# protection.net
KiCad netlist of a schematic drawn in Altium Designer
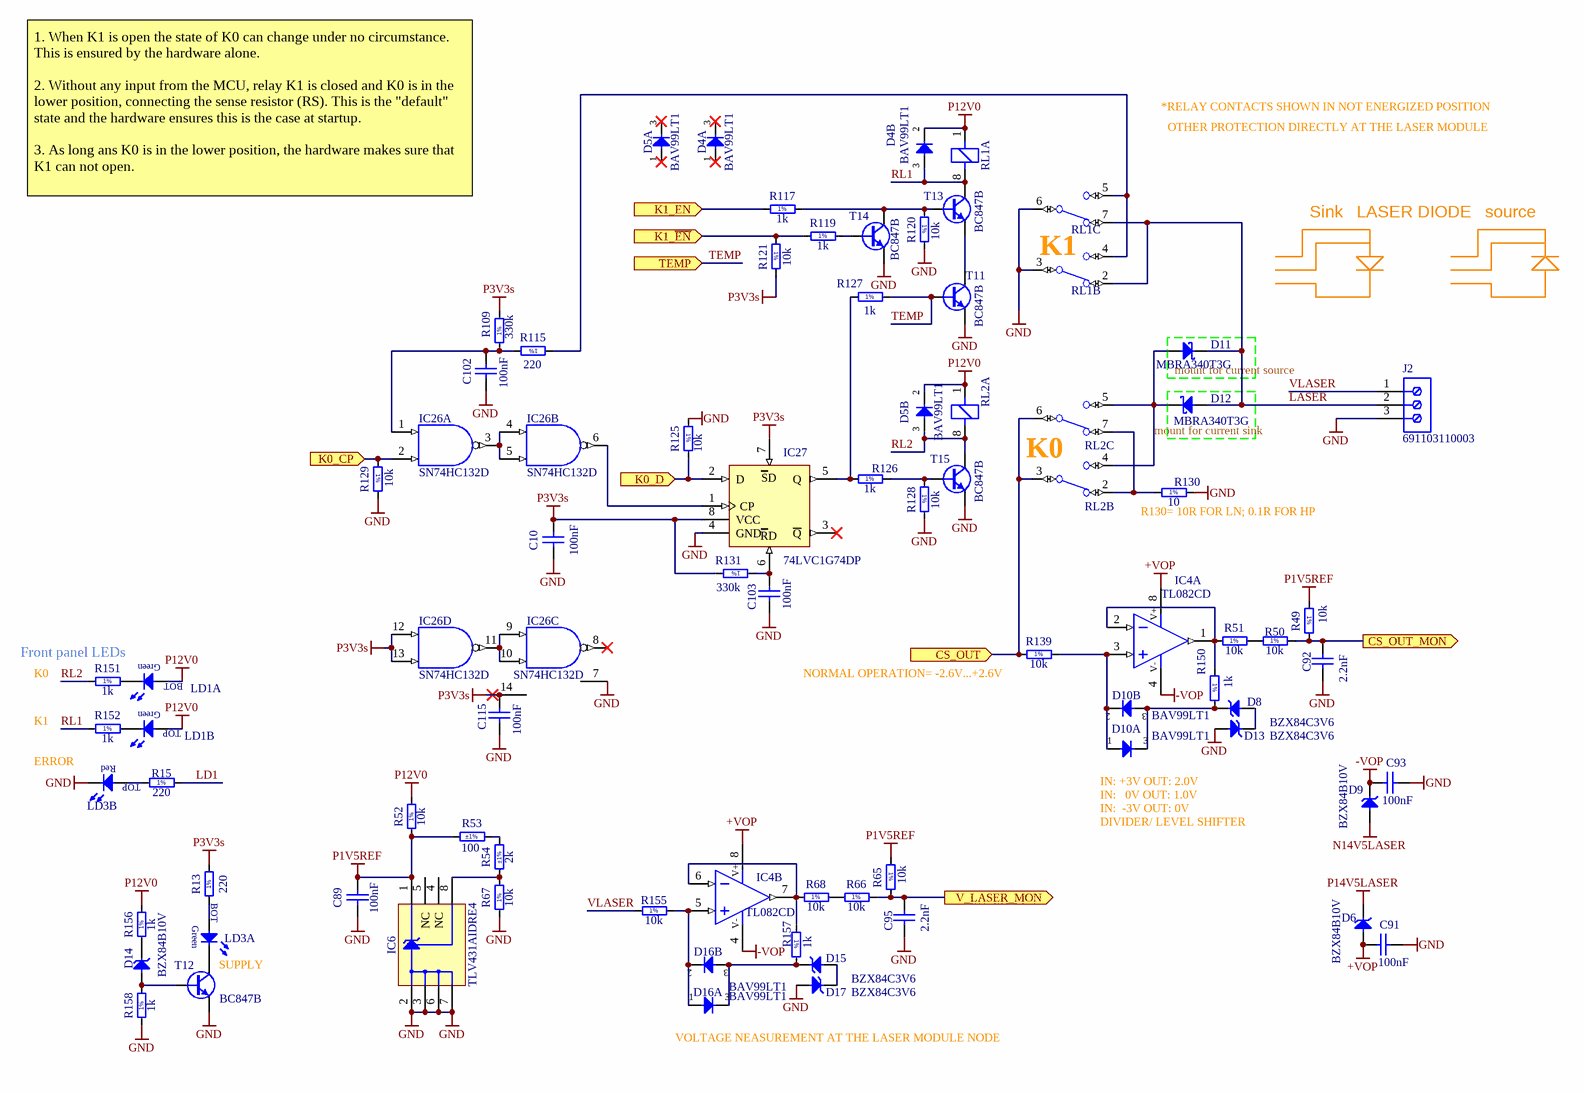
[diagram p0: protection.SchDoc]

(export (version "E")
  (design (tool "Eeschema 10.0.6"))
  (components
    (comp (ref "C10")
      (value "100nF")
      (footprint "CAPC1608X87N")
      (description "Non-polarised capacitor")
      (fields
        (field (name "PART NUMBER") "CC0603_100NF_50V_10%_X7R")
        (field (name "VOLTAGE") "50V")
        (field (name "AUTHOR") "CERN DEM JLC")
      )
      (libsource (lib "Capacitors") (part "Capacitor - non polarized"))
    )
    (comp (ref "C89")
      (value "100nF")
      (footprint "CAPC1608X87N")
      (description "Non-polarised capacitor")
      (fields
        (field (name "PART NUMBER") "CC0603_100NF_50V_10%_X7R")
        (field (name "VOLTAGE") "50V")
        (field (name "AUTHOR") "CERN DEM JLC")
      )
      (libsource (lib "Capacitors") (part "Capacitor - non polarized"))
    )
    (comp (ref "C91")
      (value "100nF")
      (footprint "CAPC1608X87N")
      (description "Non-polarised capacitor")
      (fields
        (field (name "PART NUMBER") "CC0603_100NF_50V_10%_X7R")
        (field (name "VOLTAGE") "50V")
        (field (name "AUTHOR") "CERN DEM JLC")
      )
      (libsource (lib "Capacitors") (part "Capacitor - non polarized"))
    )
    (comp (ref "C92")
      (value "2.2nF")
      (footprint "CAPC1608X87N")
      (description "Non-polarised capacitor")
      (fields
        (field (name "PART NUMBER") "CC0603_2.2NF_50V_5%_C0G")
        (field (name "VOLTAGE") "50V")
        (field (name "AUTHOR") "CERN DEM JMW")
      )
      (libsource (lib "Capacitors") (part "Capacitor - non polarized"))
    )
    (comp (ref "C93")
      (value "100nF")
      (footprint "CAPC1608X87N")
      (description "Non-polarised capacitor")
      (fields
        (field (name "PART NUMBER") "CC0603_100NF_50V_10%_X7R")
        (field (name "VOLTAGE") "50V")
        (field (name "AUTHOR") "CERN DEM JLC")
      )
      (libsource (lib "Capacitors") (part "Capacitor - non polarized"))
    )
    (comp (ref "C95")
      (value "2.2nF")
      (footprint "CAPC1608X87N")
      (description "Non-polarised capacitor")
      (fields
        (field (name "PART NUMBER") "CC0603_2.2NF_50V_5%_C0G")
        (field (name "VOLTAGE") "50V")
        (field (name "AUTHOR") "CERN DEM JMW")
      )
      (libsource (lib "Capacitors") (part "Capacitor - non polarized"))
    )
    (comp (ref "C102")
      (value "100nF")
      (footprint "CAPC1608X87N")
      (description "Non-polarised capacitor")
      (fields
        (field (name "PART NUMBER") "CC0603_100NF_50V_10%_X7R")
        (field (name "VOLTAGE") "50V")
        (field (name "AUTHOR") "CERN DEM JLC")
      )
      (libsource (lib "Capacitors") (part "Capacitor - non polarized"))
    )
    (comp (ref "C103")
      (value "100nF")
      (footprint "CAPC1608X87N")
      (description "Non-polarised capacitor")
      (fields
        (field (name "PART NUMBER") "CC0603_100NF_50V_10%_X7R")
        (field (name "VOLTAGE") "50V")
        (field (name "AUTHOR") "CERN DEM JLC")
      )
      (libsource (lib "Capacitors") (part "Capacitor - non polarized"))
    )
    (comp (ref "C115")
      (value "100nF")
      (footprint "CAPC1608X87N")
      (description "Non-polarised capacitor")
      (fields
        (field (name "PART NUMBER") "CC0603_100NF_50V_10%_X7R")
        (field (name "VOLTAGE") "50V")
        (field (name "AUTHOR") "CERN DEM JLC")
      )
      (libsource (lib "Capacitors") (part "Capacitor - non polarized"))
    )
    (comp (ref "D4")
      (value "BAV99LT1")
      (footprint "SOT95P240X110-3N")
      (description "Serial Diode")
      (fields
        (field (name "VOLTAGE") "70V")
        (field (name "POWER") "225mW")
        (field (name "AUTHOR") "CERN DEM JLC")
      )
      (libsource (lib "ICs And Semiconductors") (part "Diode x2 A1C3_A3C2"))
    )
    (comp (ref "D5")
      (value "BAV99LT1")
      (footprint "SOT95P240X110-3N")
      (description "Serial Diode")
      (fields
        (field (name "VOLTAGE") "70V")
        (field (name "POWER") "225mW")
        (field (name "AUTHOR") "CERN DEM JLC")
      )
      (libsource (lib "ICs And Semiconductors") (part "Diode x2 A1C3_A3C2"))
    )
    (comp (ref "D6")
      (value "BZX84B10V")
      (footprint "SOT95P248X115-3N")
      (description "Diode Zener Anode Pin 1 Cathode Pin 3 (Pas de pin 2)")
      (fields
        (field (name "VOLTAGE") "10V")
        (field (name "POWER") "300mW")
        (field (name "AUTHOR") "CERN DEM JLC")
      )
      (libsource (lib "ICs And Semiconductors") (part "Diode Zener A1C3"))
    )
    (comp (ref "D8")
      (value "BZX84C3V6")
      (footprint "SOT95P240X130-3N")
      (description "Diode Zener Anode Pin 1 Cathode Pin 3 (Pas de pin 2)")
      (fields
        (field (name "VOLTAGE") "3V6")
        (field (name "POWER") "350mW")
        (field (name "AUTHOR") "CERN DEM JLC")
      )
      (libsource (lib "ICs And Semiconductors") (part "Diode Zener A1C3"))
    )
    (comp (ref "D9")
      (value "BZX84B10V")
      (footprint "SOT95P248X115-3N")
      (description "Diode Zener Anode Pin 1 Cathode Pin 3 (Pas de pin 2)")
      (fields
        (field (name "VOLTAGE") "10V")
        (field (name "POWER") "300mW")
        (field (name "AUTHOR") "CERN DEM JLC")
      )
      (libsource (lib "ICs And Semiconductors") (part "Diode Zener A1C3"))
    )
    (comp (ref "D10")
      (value "BAV99LT1")
      (footprint "SOT95P240X110-3N")
      (description "Serial Diode")
      (fields
        (field (name "VOLTAGE") "70V")
        (field (name "POWER") "225mW")
        (field (name "AUTHOR") "CERN DEM JLC")
      )
      (libsource (lib "ICs And Semiconductors") (part "Diode x2 A1C3_A3C2"))
    )
    (comp (ref "D11")
      (value "MBRA340T3G")
      (footprint "DIOM5226X220N")
      (description "Schottky Diode")
      (fields
        (field (name "VOLTAGE") "40V")
        (field (name "POWER") "3A")
        (field (name "AUTHOR") "CERN DEM JLC")
      )
      (libsource (lib "ICs And Semiconductors") (part "Diode Schottky"))
    )
    (comp (ref "D12")
      (value "MBRA340T3G")
      (footprint "DIOM5226X220N")
      (description "Schottky Diode")
      (fields
        (field (name "VOLTAGE") "40V")
        (field (name "POWER") "3A")
        (field (name "AUTHOR") "CERN DEM JLC")
      )
      (libsource (lib "ICs And Semiconductors") (part "Diode Schottky"))
    )
    (comp (ref "D13")
      (value "BZX84C3V6")
      (footprint "SOT95P240X130-3N")
      (description "Diode Zener Anode Pin 1 Cathode Pin 3 (Pas de pin 2)")
      (fields
        (field (name "VOLTAGE") "3V6")
        (field (name "POWER") "350mW")
        (field (name "AUTHOR") "CERN DEM JLC")
      )
      (libsource (lib "ICs And Semiconductors") (part "Diode Zener A1C3"))
    )
    (comp (ref "D14")
      (value "BZX84B10V")
      (footprint "SOT95P248X115-3N")
      (description "Diode Zener Anode Pin 1 Cathode Pin 3 (Pas de pin 2)")
      (fields
        (field (name "VOLTAGE") "10V")
        (field (name "POWER") "300mW")
        (field (name "AUTHOR") "CERN DEM JLC")
      )
      (libsource (lib "ICs And Semiconductors") (part "Diode Zener A1C3"))
    )
    (comp (ref "D15")
      (value "BZX84C3V6")
      (footprint "SOT95P240X130-3N")
      (description "Diode Zener Anode Pin 1 Cathode Pin 3 (Pas de pin 2)")
      (fields
        (field (name "VOLTAGE") "3V6")
        (field (name "POWER") "350mW")
        (field (name "AUTHOR") "CERN DEM JLC")
      )
      (libsource (lib "ICs And Semiconductors") (part "Diode Zener A1C3"))
    )
    (comp (ref "D16")
      (value "BAV99LT1")
      (footprint "SOT95P240X110-3N")
      (description "Serial Diode")
      (fields
        (field (name "VOLTAGE") "70V")
        (field (name "POWER") "225mW")
        (field (name "AUTHOR") "CERN DEM JLC")
      )
      (libsource (lib "ICs And Semiconductors") (part "Diode x2 A1C3_A3C2"))
    )
    (comp (ref "D17")
      (value "BZX84C3V6")
      (footprint "SOT95P240X130-3N")
      (description "Diode Zener Anode Pin 1 Cathode Pin 3 (Pas de pin 2)")
      (fields
        (field (name "VOLTAGE") "3V6")
        (field (name "POWER") "350mW")
        (field (name "AUTHOR") "CERN DEM JLC")
      )
      (libsource (lib "ICs And Semiconductors") (part "Diode Zener A1C3"))
    )
    (comp (ref "IC4")
      (value "TL082CD")
      (footprint "SOIC127P600X175-8N")
      (description "Dual Operational Amplifier")
      (fields (field (name "MANUFACTURER") "TEXAS INSTRUMENTS") (field (name "AUTHOR") "CERN DEM JLC"))
      (libsource (lib "ICs And Semiconductors") (part "Operational Amplifier x2 Type1"))
    )
    (comp (ref "IC6")
      (value "TLV431AIDRE4")
      (footprint "SOIC127P600X175-8N")
      (description "Precision Programmable Reference")
      (fields (field (name "MANUFACTURER") "TEXAS INSTRUMENTS") (field (name "AUTHOR") "CERN DEM JLC"))
      (libsource (lib "ICs And Semiconductors") (part "TL431xD"))
    )
    (comp (ref "IC26")
      (value "SN74HC132D")
      (footprint "SOIC127P600X175-14N")
      (description "Quad Positive NAND Gate With Schmitt-Trigger Input")
      (fields (field (name "MANUFACTURER") "TEXAS INSTRUMENTS") (field (name "AUTHOR") "CERN DEM JLC"))
      (libsource (lib "") (part "74132_1"))
    )
    (comp (ref "IC27")
      (value "74LVC1G74DP")
      (footprint "SOP65P400X110-8N")
      (description "Single D-type flip-flop with set and reset, positive edge trigger")
      (fields (field (name "MANUFACTURER") "NXP SEMICONDUCTORS") (field (name "AUTHOR") "CERN DEM JLC"))
      (libsource (lib "ICs And Semiconductors") (part "741G74"))
    )
    (comp (ref "J2")
      (value "691103110003")
      (footprint "691103110003")
      (description "WR-TBL Serie 1031 Horizontal Entry Modular, Pressure Clamp, THT, pitch 3.5mm, 3p")
      (fields (field (name "MANUFACTURER") "Wurth Elektronik"))
      (libsource (lib "Altium_WR-TBL (rev21a)") (part "691103110003"))
    )
    (comp (ref "LD1")
      (value "Green/Green")
      (footprint "LED_DIALIGHT_571-0122F")
      (description "LED x2 Green 1C2A-BOT_3C4A-TOP")
      (fields
        (field (name "PART NUMBER") "LED_DIALIGHT_571-0122F")
        (field (name "MANUFACTURER") "DIALIGHT")
        (field (name "AUTHOR") "CERN DEM JLC")
      )
      (libsource (lib "ICs And Semiconductors") (part "LED x2 Green 1C2A-BOT_3C4A-TOP"))
    )
    (comp (ref "LD3")
      (value "Red/Green")
      (footprint "LED_DIALIGHT_571-0112F")
      (description "2x LED  Botom Green, Top Red")
      (fields
        (field (name "PART NUMBER") "LED_DIALIGHT_571-0112F")
        (field (name "MANUFACTURER") "DIALIGHT")
        (field (name "AUTHOR") "CERN DEM JLC")
      )
      (libsource (lib "ICs And Semiconductors") (part "LED x2 G-1C2A-BOT_R-3C4A-TOP"))
    )
    (comp (ref "R13")
      (value "220")
      (footprint "RESC1608X55N")
      (description "Resistor - 1%")
      (fields
        (field (name "PART NUMBER") "R0603_220R_1%_0.1W_100PPM")
        (field (name "POWER") "0.1W")
        (field (name "AUTHOR") "CERN DEM JLC")
      )
      (libsource (lib "Resistors") (part "Resistor - 1%"))
    )
    (comp (ref "R15")
      (value "220")
      (footprint "RESC1608X55N")
      (description "Resistor - 1%")
      (fields
        (field (name "PART NUMBER") "R0603_220R_1%_0.1W_100PPM")
        (field (name "POWER") "0.1W")
        (field (name "AUTHOR") "CERN DEM JLC")
      )
      (libsource (lib "Resistors") (part "Resistor - 1%"))
    )
    (comp (ref "R49")
      (value "10k")
      (footprint "RESC1608X55N")
      (description "Resistor - 1%")
      (fields
        (field (name "PART NUMBER") "R0603_10K_1%_0.1W_100PPM")
        (field (name "POWER") "0.1W")
        (field (name "AUTHOR") "CERN DEM JLC")
      )
      (libsource (lib "Resistors") (part "Resistor - 1%"))
    )
    (comp (ref "R50")
      (value "10k")
      (footprint "RESC1608X55N")
      (description "Resistor - 1%")
      (fields
        (field (name "PART NUMBER") "R0603_10K_1%_0.1W_100PPM")
        (field (name "POWER") "0.1W")
        (field (name "AUTHOR") "CERN DEM JLC")
      )
      (libsource (lib "Resistors") (part "Resistor - 1%"))
    )
    (comp (ref "R51")
      (value "10k")
      (footprint "RESC1608X55N")
      (description "Resistor - 1%")
      (fields
        (field (name "PART NUMBER") "R0603_10K_1%_0.1W_100PPM")
        (field (name "POWER") "0.1W")
        (field (name "AUTHOR") "CERN DEM JLC")
      )
      (libsource (lib "Resistors") (part "Resistor - 1%"))
    )
    (comp (ref "R52")
      (value "10k")
      (footprint "RESC1608X55N")
      (description "Resistor - 1%")
      (fields
        (field (name "PART NUMBER") "R0603_10K_1%_0.1W_100PPM")
        (field (name "POWER") "0.1W")
        (field (name "AUTHOR") "CERN DEM JLC")
      )
      (libsource (lib "Resistors") (part "Resistor - 1%"))
    )
    (comp (ref "R53")
      (value "100")
      (footprint "RESC1608X55N")
      (description "Resistor - 1%")
      (fields
        (field (name "TOLERANCE") "±1%")
        (field (name "PART NUMBER") "R0603_100R_1%_0.1W_100PPM")
        (field (name "POWER") "0.1W")
        (field (name "AUTHOR") "CERN DEM JLC")
      )
      (libsource (lib "Resistors") (part "Resistor - 1%"))
    )
    (comp (ref "R54")
      (value "2k")
      (footprint "RESC1608X55N")
      (description "Resistor - 1%")
      (fields
        (field (name "TOLERANCE") "±1%")
        (field (name "PART NUMBER") "R0603_2K_1%_0.1W_100PPM")
        (field (name "POWER") "0.1W")
        (field (name "AUTHOR") "CERN DEM JLC")
      )
      (libsource (lib "Resistors") (part "Resistor - 1%"))
    )
    (comp (ref "R65")
      (value "10k")
      (footprint "RESC1608X55N")
      (description "Resistor - 1%")
      (fields
        (field (name "PART NUMBER") "R0603_10K_1%_0.1W_100PPM")
        (field (name "POWER") "0.1W")
        (field (name "AUTHOR") "CERN DEM JLC")
      )
      (libsource (lib "Resistors") (part "Resistor - 1%"))
    )
    (comp (ref "R66")
      (value "10k")
      (footprint "RESC1608X55N")
      (description "Resistor - 1%")
      (fields
        (field (name "PART NUMBER") "R0603_10K_1%_0.1W_100PPM")
        (field (name "POWER") "0.1W")
        (field (name "AUTHOR") "CERN DEM JLC")
      )
      (libsource (lib "Resistors") (part "Resistor - 1%"))
    )
    (comp (ref "R67")
      (value "10k")
      (footprint "RESC1608X55N")
      (description "Resistor - 1%")
      (fields
        (field (name "PART NUMBER") "R0603_10K_1%_0.1W_100PPM")
        (field (name "POWER") "0.1W")
        (field (name "AUTHOR") "CERN DEM JLC")
      )
      (libsource (lib "Resistors") (part "Resistor - 1%"))
    )
    (comp (ref "R68")
      (value "10k")
      (footprint "RESC1608X55N")
      (description "Resistor - 1%")
      (fields
        (field (name "PART NUMBER") "R0603_10K_1%_0.1W_100PPM")
        (field (name "POWER") "0.1W")
        (field (name "AUTHOR") "CERN DEM JLC")
      )
      (libsource (lib "Resistors") (part "Resistor - 1%"))
    )
    (comp (ref "R109")
      (value "330k")
      (footprint "RESC1608X55N")
      (description "Resistor - 1%")
      (fields
        (field (name "PART NUMBER") "R0603_330K_1%_0.1W_100PPM")
        (field (name "POWER") "0.1W")
        (field (name "AUTHOR") "CERN DEM JLC")
      )
      (libsource (lib "Resistors") (part "Resistor - 1%"))
    )
    (comp (ref "R115")
      (value "220")
      (footprint "RESC1608X55N")
      (description "Resistor - 1%")
      (fields
        (field (name "PART NUMBER") "R0603_220R_1%_0.1W_100PPM")
        (field (name "POWER") "0.1W")
        (field (name "AUTHOR") "CERN DEM JLC")
      )
      (libsource (lib "Resistors") (part "Resistor - 1%"))
    )
    (comp (ref "R117")
      (value "1k")
      (footprint "RESC1608X55N")
      (description "Resistor - 1%")
      (fields
        (field (name "PART NUMBER") "R0603_1K_1%_0.1W_100PPM")
        (field (name "POWER") "0.1W")
        (field (name "AUTHOR") "CERN DEM JLC")
      )
      (libsource (lib "Resistors") (part "Resistor - 1%"))
    )
    (comp (ref "R119")
      (value "1k")
      (footprint "RESC1608X55N")
      (description "Resistor - 1%")
      (fields
        (field (name "PART NUMBER") "R0603_1K_1%_0.1W_100PPM")
        (field (name "POWER") "0.1W")
        (field (name "AUTHOR") "CERN DEM JLC")
      )
      (libsource (lib "Resistors") (part "Resistor - 1%"))
    )
    (comp (ref "R120")
      (value "10k")
      (footprint "RESC1608X55N")
      (description "Resistor - 1%")
      (fields
        (field (name "PART NUMBER") "R0603_10K_1%_0.1W_100PPM")
        (field (name "POWER") "0.1W")
        (field (name "AUTHOR") "CERN DEM JLC")
      )
      (libsource (lib "Resistors") (part "Resistor - 1%"))
    )
    (comp (ref "R121")
      (value "10k")
      (footprint "RESC1608X55N")
      (description "Resistor - 1%")
      (fields
        (field (name "PART NUMBER") "R0603_10K_1%_0.1W_100PPM")
        (field (name "POWER") "0.1W")
        (field (name "AUTHOR") "CERN DEM JLC")
      )
      (libsource (lib "Resistors") (part "Resistor - 1%"))
    )
    (comp (ref "R125")
      (value "10k")
      (footprint "RESC1608X55N")
      (description "Resistor - 1%")
      (fields
        (field (name "PART NUMBER") "R0603_10K_1%_0.1W_100PPM")
        (field (name "POWER") "0.1W")
        (field (name "AUTHOR") "CERN DEM JLC")
      )
      (libsource (lib "Resistors") (part "Resistor - 1%"))
    )
    (comp (ref "R126")
      (value "1k")
      (footprint "RESC1608X55N")
      (description "Resistor - 1%")
      (fields
        (field (name "PART NUMBER") "R0603_1K_1%_0.1W_100PPM")
        (field (name "POWER") "0.1W")
        (field (name "AUTHOR") "CERN DEM JLC")
      )
      (libsource (lib "Resistors") (part "Resistor - 1%"))
    )
    (comp (ref "R127")
      (value "1k")
      (footprint "RESC1608X55N")
      (description "Resistor - 1%")
      (fields
        (field (name "PART NUMBER") "R0603_1K_1%_0.1W_100PPM")
        (field (name "POWER") "0.1W")
        (field (name "AUTHOR") "CERN DEM JLC")
      )
      (libsource (lib "Resistors") (part "Resistor - 1%"))
    )
    (comp (ref "R128")
      (value "10k")
      (footprint "RESC1608X55N")
      (description "Resistor - 1%")
      (fields
        (field (name "PART NUMBER") "R0603_10K_1%_0.1W_100PPM")
        (field (name "POWER") "0.1W")
        (field (name "AUTHOR") "CERN DEM JLC")
      )
      (libsource (lib "Resistors") (part "Resistor - 1%"))
    )
    (comp (ref "R129")
      (value "10k")
      (footprint "RESC1608X55N")
      (description "Resistor - 1%")
      (fields
        (field (name "PART NUMBER") "R0603_10K_1%_0.1W_100PPM")
        (field (name "POWER") "0.1W")
        (field (name "AUTHOR") "CERN DEM JLC")
      )
      (libsource (lib "Resistors") (part "Resistor - 1%"))
    )
    (comp (ref "R130")
      (value "10")
      (footprint "RES1016-630X250")
      (description "Resistor - 1%")
      (fields
        (field (name "PART NUMBER") "RMF_10R_1%_0.6W_50PPM_1016-630X250")
        (field (name "POWER") "0.6W")
        (field (name "AUTHOR") "CERN DEM JLC")
      )
      (libsource (lib "Resistors") (part "Resistor - 1%"))
    )
    (comp (ref "R131")
      (value "330k")
      (footprint "RESC1608X55N")
      (description "Resistor - 1%")
      (fields
        (field (name "PART NUMBER") "R0603_330K_1%_0.1W_100PPM")
        (field (name "POWER") "0.1W")
        (field (name "AUTHOR") "CERN DEM JLC")
      )
      (libsource (lib "Resistors") (part "Resistor - 1%"))
    )
    (comp (ref "R139")
      (value "10k")
      (footprint "RESC1608X55N")
      (description "Resistor - 1%")
      (fields
        (field (name "PART NUMBER") "R0603_10K_1%_0.1W_100PPM")
        (field (name "POWER") "0.1W")
        (field (name "AUTHOR") "CERN DEM JLC")
      )
      (libsource (lib "Resistors") (part "Resistor - 1%"))
    )
    (comp (ref "R150")
      (value "1k")
      (footprint "RESC1608X55N")
      (description "Resistor - 1%")
      (fields
        (field (name "PART NUMBER") "R0603_1K_1%_0.1W_100PPM")
        (field (name "POWER") "0.1W")
        (field (name "AUTHOR") "CERN DEM JLC")
      )
      (libsource (lib "Resistors") (part "Resistor - 1%"))
    )
    (comp (ref "R151")
      (value "1k")
      (footprint "RESC1608X55N")
      (description "Resistor - 1%")
      (fields
        (field (name "PART NUMBER") "R0603_1K_1%_0.1W_100PPM")
        (field (name "POWER") "0.1W")
        (field (name "AUTHOR") "CERN DEM JLC")
      )
      (libsource (lib "Resistors") (part "Resistor - 1%"))
    )
    (comp (ref "R152")
      (value "1k")
      (footprint "RESC1608X55N")
      (description "Resistor - 1%")
      (fields
        (field (name "PART NUMBER") "R0603_1K_1%_0.1W_100PPM")
        (field (name "POWER") "0.1W")
        (field (name "AUTHOR") "CERN DEM JLC")
      )
      (libsource (lib "Resistors") (part "Resistor - 1%"))
    )
    (comp (ref "R155")
      (value "10k")
      (footprint "RESC1608X55N")
      (description "Resistor - 1%")
      (fields
        (field (name "PART NUMBER") "R0603_10K_1%_0.1W_100PPM")
        (field (name "POWER") "0.1W")
        (field (name "AUTHOR") "CERN DEM JLC")
      )
      (libsource (lib "Resistors") (part "Resistor - 1%"))
    )
    (comp (ref "R156")
      (value "1k")
      (footprint "RESC1608X55N")
      (description "Resistor - 1%")
      (fields
        (field (name "PART NUMBER") "R0603_1K_1%_0.1W_100PPM")
        (field (name "POWER") "0.1W")
        (field (name "AUTHOR") "CERN DEM JLC")
      )
      (libsource (lib "Resistors") (part "Resistor - 1%"))
    )
    (comp (ref "R157")
      (value "1k")
      (footprint "RESC1608X55N")
      (description "Resistor - 1%")
      (fields
        (field (name "PART NUMBER") "R0603_1K_1%_0.1W_100PPM")
        (field (name "POWER") "0.1W")
        (field (name "AUTHOR") "CERN DEM JLC")
      )
      (libsource (lib "Resistors") (part "Resistor - 1%"))
    )
    (comp (ref "R158")
      (value "1k")
      (footprint "RESC1608X55N")
      (description "Resistor - 1%")
      (fields
        (field (name "PART NUMBER") "R0603_1K_1%_0.1W_100PPM")
        (field (name "POWER") "0.1W")
        (field (name "AUTHOR") "CERN DEM JLC")
      )
      (libsource (lib "Resistors") (part "Resistor - 1%"))
    )
    (comp (ref "RL1")
      (value "REL_OMRON_G2RL-24")
      (footprint "REL_OMRON_G2RL-24")
      (description "DPDT Power Relay, G2RL Series")
      (fields
        (field (name "PART NUMBER") "REL_OMRON_G2RL-24-DC12")
        (field (name "MANUFACTURER") "OMRON ELECTRONIC")
        (field (name "AUTHOR") "CERN DEM JMW")
      )
      (libsource (lib "") (part "REL_OMRON_G2RL-24_2"))
    )
    (comp (ref "RL2")
      (value "REL_OMRON_G2RL-24")
      (footprint "REL_OMRON_G2RL-24")
      (description "DPDT Power Relay, G2RL Series")
      (fields
        (field (name "PART NUMBER") "REL_OMRON_G2RL-24-DC12")
        (field (name "MANUFACTURER") "OMRON ELECTRONIC")
        (field (name "AUTHOR") "CERN DEM JMW")
      )
      (libsource (lib "") (part "REL_OMRON_G2RL-24_1"))
    )
    (comp (ref "T11")
      (value "BC847B")
      (footprint "SOT95P230X110-3N")
      (description "NPN Transistor")
      (fields (field (name "MANUFACTURER") "NXP SEMICONDUCTORS") (field (name "AUTHOR") "CERN DEM JLC"))
      (libsource (lib "ICs And Semiconductors") (part "NPN B1 E2 C3"))
    )
    (comp (ref "T12")
      (value "BC847B")
      (footprint "SOT95P230X110-3N")
      (description "NPN Transistor")
      (fields (field (name "MANUFACTURER") "NXP SEMICONDUCTORS") (field (name "AUTHOR") "CERN DEM JLC"))
      (libsource (lib "ICs And Semiconductors") (part "NPN B1 E2 C3"))
    )
    (comp (ref "T13")
      (value "BC847B")
      (footprint "SOT95P230X110-3N")
      (description "NPN Transistor")
      (fields (field (name "MANUFACTURER") "NXP SEMICONDUCTORS") (field (name "AUTHOR") "CERN DEM JLC"))
      (libsource (lib "ICs And Semiconductors") (part "NPN B1 E2 C3"))
    )
    (comp (ref "T14")
      (value "BC847B")
      (footprint "SOT95P230X110-3N")
      (description "NPN Transistor")
      (fields (field (name "MANUFACTURER") "NXP SEMICONDUCTORS") (field (name "AUTHOR") "CERN DEM JLC"))
      (libsource (lib "ICs And Semiconductors") (part "NPN B1 E2 C3"))
    )
    (comp (ref "T15")
      (value "BC847B")
      (footprint "SOT95P230X110-3N")
      (description "NPN Transistor")
      (fields (field (name "MANUFACTURER") "NXP SEMICONDUCTORS") (field (name "AUTHOR") "CERN DEM JLC"))
      (libsource (lib "ICs And Semiconductors") (part "NPN B1 E2 C3"))
    )
  )
  (nets
    (net (code "1") (name "+VOP") (class "Default")
      (node (ref "C91") (pin "1") (pinfunction "1_1") (pintype "passive"))
      (node (ref "D6") (pin "1") (pinfunction "A_1") (pintype "passive"))
      (node (ref "IC4") (pin "8") (pinfunction "V+_8") (pintype "power_in"))
    )
    (net (code "2") (name "-VOP") (class "Default")
      (node (ref "C93") (pin "1") (pinfunction "1_1") (pintype "passive"))
      (node (ref "D9") (pin "3") (pinfunction "C_3") (pintype "passive"))
      (node (ref "IC4") (pin "4") (pinfunction "V-_4") (pintype "power_in"))
    )
    (net (code "3") (name "/CS_OUT") (class "Default")
      (node (ref "R139") (pin "1") (pinfunction "1_1") (pintype "passive"))
      (node (ref "RL2") (pin "3") (pinfunction "C_3") (pintype "bidirectional"))
      (node (ref "RL2") (pin "6") (pinfunction "C_6") (pintype "bidirectional"))
    )
    (net (code "4") (name "/CS_OUT_MON") (class "Default")
      (node (ref "C92") (pin "2") (pinfunction "2_2") (pintype "passive"))
      (node (ref "R49") (pin "2") (pinfunction "2_2") (pintype "passive"))
      (node (ref "R50") (pin "2") (pinfunction "2_2") (pintype "passive"))
    )
    (net (code "5") (name "/K0_CP") (class "Default")
      (node (ref "IC26") (pin "2") (pinfunction "B_2") (pintype "input"))
      (node (ref "R129") (pin "1") (pinfunction "1_1") (pintype "passive"))
    )
    (net (code "6") (name "/K0_D") (class "Default")
      (node (ref "IC27") (pin "2") (pinfunction "D_2") (pintype "input"))
      (node (ref "R125") (pin "2") (pinfunction "2_2") (pintype "passive"))
    )
    (net (code "7") (name "/K1_EN") (class "Default")
      (node (ref "R117") (pin "1") (pinfunction "1_1") (pintype "passive"))
    )
    (net (code "8") (name "/K1_~{EN}") (class "Default")
      (node (ref "R119") (pin "1") (pinfunction "1_1") (pintype "passive"))
      (node (ref "R121") (pin "1") (pinfunction "1_1") (pintype "passive"))
    )
    (net (code "9") (name "/LASER") (class "Default")
      (node (ref "D11") (pin "1") (pinfunction "C_1") (pintype "passive"))
      (node (ref "D12") (pin "2") (pinfunction "A_2") (pintype "passive"))
      (node (ref "J2") (pin "2") (pinfunction "2_2") (pintype "passive"))
      (node (ref "RL1") (pin "2") (pinfunction "NC_2") (pintype "bidirectional"))
      (node (ref "RL1") (pin "7") (pinfunction "NC_7") (pintype "bidirectional"))
    )
    (net (code "10") (name "/LD1") (class "Default")
      (node (ref "R15") (pin "2") (pinfunction "2_2") (pintype "passive"))
    )
    (net (code "11") (name "/RL1") (class "Default")
      (node (ref "D4") (pin "3") (pinfunction "COMAC_3") (pintype "passive"))
      (node (ref "R152") (pin "1") (pinfunction "1_1") (pintype "passive"))
      (node (ref "RL1") (pin "8") (pinfunction "8_8") (pintype "passive"))
      (node (ref "T13") (pin "3") (pinfunction "C_3") (pintype "passive"))
    )
    (net (code "12") (name "/RL2") (class "Default")
      (node (ref "D5") (pin "3") (pinfunction "COMAC_3") (pintype "passive"))
      (node (ref "R151") (pin "1") (pinfunction "1_1") (pintype "passive"))
      (node (ref "RL2") (pin "8") (pinfunction "8_8") (pintype "passive"))
      (node (ref "T15") (pin "3") (pinfunction "C_3") (pintype "passive"))
    )
    (net (code "13") (name "/TEMP") (class "Default")
      (node (ref "R127") (pin "2") (pinfunction "2_2") (pintype "passive"))
      (node (ref "T11") (pin "1") (pinfunction "B_1") (pintype "passive"))
    )
    (net (code "14") (name "/VLASER") (class "Default")
      (node (ref "J2") (pin "1") (pinfunction "1_1") (pintype "passive"))
      (node (ref "R155") (pin "1") (pinfunction "1_1") (pintype "passive"))
    )
    (net (code "15") (name "/V_LASER_MON") (class "Default")
      (node (ref "C95") (pin "2") (pinfunction "2_2") (pintype "passive"))
      (node (ref "R65") (pin "2") (pinfunction "2_2") (pintype "passive"))
      (node (ref "R66") (pin "2") (pinfunction "2_2") (pintype "passive"))
    )
    (net (code "16") (name "GND") (class "Default")
      (node (ref "C10") (pin "1") (pinfunction "1_1") (pintype "passive"))
      (node (ref "C102") (pin "1") (pinfunction "1_1") (pintype "passive"))
      (node (ref "C103") (pin "1") (pinfunction "1_1") (pintype "passive"))
      (node (ref "C115") (pin "1") (pinfunction "1_1") (pintype "passive"))
      (node (ref "C89") (pin "1") (pinfunction "1_1") (pintype "passive"))
      (node (ref "C91") (pin "2") (pinfunction "2_2") (pintype "passive"))
      (node (ref "C92") (pin "1") (pinfunction "1_1") (pintype "passive"))
      (node (ref "C93") (pin "2") (pinfunction "2_2") (pintype "passive"))
      (node (ref "C95") (pin "1") (pinfunction "1_1") (pintype "passive"))
      (node (ref "D13") (pin "1") (pinfunction "A_1") (pintype "passive"))
      (node (ref "D17") (pin "1") (pinfunction "A_1") (pintype "passive"))
      (node (ref "IC26") (pin "7") (pinfunction "GND_7") (pintype "power_in"))
      (node (ref "IC27") (pin "4") (pinfunction "GND_4") (pintype "power_in"))
      (node (ref "IC6") (pin "2") (pinfunction "A_2") (pintype "passive"))
      (node (ref "IC6") (pin "3") (pinfunction "A_3") (pintype "passive"))
      (node (ref "IC6") (pin "6") (pinfunction "A_6") (pintype "passive"))
      (node (ref "IC6") (pin "7") (pinfunction "A_7") (pintype "passive"))
      (node (ref "J2") (pin "3") (pinfunction "3_3") (pintype "passive"))
      (node (ref "LD3") (pin "3") (pinfunction "C_3") (pintype "passive"))
      (node (ref "R120") (pin "2") (pinfunction "2_2") (pintype "passive"))
      (node (ref "R125") (pin "1") (pinfunction "1_1") (pintype "passive"))
      (node (ref "R128") (pin "2") (pinfunction "2_2") (pintype "passive"))
      (node (ref "R129") (pin "2") (pinfunction "2_2") (pintype "passive"))
      (node (ref "R130") (pin "2") (pinfunction "2_2") (pintype "passive"))
      (node (ref "R158") (pin "1") (pinfunction "1_1") (pintype "passive"))
      (node (ref "R67") (pin "1") (pinfunction "1_1") (pintype "passive"))
      (node (ref "RL1") (pin "3") (pinfunction "C_3") (pintype "bidirectional"))
      (node (ref "RL1") (pin "6") (pinfunction "C_6") (pintype "bidirectional"))
      (node (ref "T11") (pin "2") (pinfunction "E_2") (pintype "passive"))
      (node (ref "T12") (pin "2") (pinfunction "E_2") (pintype "passive"))
      (node (ref "T14") (pin "2") (pinfunction "E_2") (pintype "passive"))
      (node (ref "T15") (pin "2") (pinfunction "E_2") (pintype "passive"))
    )
    (net (code "17") (name "N14V5LASER") (class "Default")
      (node (ref "D9") (pin "1") (pinfunction "A_1") (pintype "passive"))
    )
    (net (code "18") (name "Net-(D10A-A)") (class "Default")
      (node (ref "D10") (pin "1") (pinfunction "A_1") (pintype "passive"))
      (node (ref "D10") (pin "2") (pinfunction "C_2") (pintype "passive"))
      (node (ref "IC4") (pin "3") (pinfunction "IN+_3") (pintype "input"))
      (node (ref "R139") (pin "2") (pinfunction "2_2") (pintype "passive"))
    )
    (net (code "19") (name "Net-(D10A-COMAC)") (class "Default")
      (node (ref "D10") (pin "3") (pinfunction "COMAC_3") (pintype "passive"))
      (node (ref "D8") (pin "3") (pinfunction "C_3") (pintype "passive"))
      (node (ref "R150") (pin "2") (pinfunction "2_2") (pintype "passive"))
    )
    (net (code "20") (name "Net-(D11-A)") (class "Default")
      (node (ref "D11") (pin "2") (pinfunction "A_2") (pintype "passive"))
      (node (ref "D12") (pin "1") (pinfunction "C_1") (pintype "passive"))
      (node (ref "RL2") (pin "4") (pinfunction "NO_4") (pintype "bidirectional"))
      (node (ref "RL2") (pin "5") (pinfunction "NO_5") (pintype "bidirectional"))
    )
    (net (code "21") (name "Net-(D13-C)") (class "Default")
      (node (ref "D13") (pin "3") (pinfunction "C_3") (pintype "passive"))
      (node (ref "D8") (pin "1") (pinfunction "A_1") (pintype "passive"))
    )
    (net (code "22") (name "Net-(D14-A)") (class "Default")
      (node (ref "D14") (pin "1") (pinfunction "A_1") (pintype "passive"))
      (node (ref "R158") (pin "2") (pinfunction "2_2") (pintype "passive"))
      (node (ref "T12") (pin "1") (pinfunction "B_1") (pintype "passive"))
    )
    (net (code "23") (name "Net-(D14-C)") (class "Default")
      (node (ref "D14") (pin "3") (pinfunction "C_3") (pintype "passive"))
      (node (ref "R156") (pin "1") (pinfunction "1_1") (pintype "passive"))
    )
    (net (code "24") (name "Net-(D15-A)") (class "Default")
      (node (ref "D15") (pin "1") (pinfunction "A_1") (pintype "passive"))
      (node (ref "D17") (pin "3") (pinfunction "C_3") (pintype "passive"))
    )
    (net (code "25") (name "Net-(D15-C)") (class "Default")
      (node (ref "D15") (pin "3") (pinfunction "C_3") (pintype "passive"))
      (node (ref "D16") (pin "3") (pinfunction "COMAC_3") (pintype "passive"))
      (node (ref "R157") (pin "2") (pinfunction "2_2") (pintype "passive"))
    )
    (net (code "26") (name "Net-(D16A-A)") (class "Default")
      (node (ref "D16") (pin "1") (pinfunction "A_1") (pintype "passive"))
      (node (ref "D16") (pin "2") (pinfunction "C_2") (pintype "passive"))
      (node (ref "IC4") (pin "5") (pinfunction "IN+_5") (pintype "input"))
      (node (ref "R155") (pin "2") (pinfunction "2_2") (pintype "passive"))
    )
    (net (code "27") (name "Net-(IC4A-IN-)") (class "Default")
      (node (ref "IC4") (pin "1") (pinfunction "OUT_1") (pintype "output"))
      (node (ref "IC4") (pin "2") (pinfunction "IN-_2") (pintype "input"))
      (node (ref "R150") (pin "1") (pinfunction "1_1") (pintype "passive"))
      (node (ref "R51") (pin "1") (pinfunction "1_1") (pintype "passive"))
    )
    (net (code "28") (name "Net-(IC4B-IN-)") (class "Default")
      (node (ref "IC4") (pin "6") (pinfunction "IN-_6") (pintype "input"))
      (node (ref "IC4") (pin "7") (pinfunction "OUT_7") (pintype "output"))
      (node (ref "R157") (pin "1") (pinfunction "1_1") (pintype "passive"))
      (node (ref "R68") (pin "1") (pinfunction "1_1") (pintype "passive"))
    )
    (net (code "29") (name "Net-(IC6-REF)") (class "Default")
      (node (ref "IC6") (pin "8") (pinfunction "REF_8") (pintype "passive"))
      (node (ref "R54") (pin "1") (pinfunction "1_1") (pintype "passive"))
      (node (ref "R67") (pin "2") (pinfunction "2_2") (pintype "passive"))
    )
    (net (code "30") (name "Net-(IC26A-A)") (class "Default")
      (node (ref "C102") (pin "2") (pinfunction "2_2") (pintype "passive"))
      (node (ref "IC26") (pin "1") (pinfunction "A_1") (pintype "input"))
      (node (ref "R109") (pin "1") (pinfunction "1_1") (pintype "passive"))
      (node (ref "R115") (pin "2") (pinfunction "2_2") (pintype "passive"))
    )
    (net (code "31") (name "Net-(IC26A-~{O})") (class "Default")
      (node (ref "IC26") (pin "3") (pinfunction "~{O}_3") (pintype "output"))
      (node (ref "IC26") (pin "4") (pinfunction "A_4") (pintype "input"))
      (node (ref "IC26") (pin "5") (pinfunction "B_5") (pintype "input"))
    )
    (net (code "32") (name "Net-(IC26B-~{O})") (class "Default")
      (node (ref "IC26") (pin "6") (pinfunction "~{O}_6") (pintype "output"))
      (node (ref "IC27") (pin "1") (pinfunction "CP_1") (pintype "input"))
    )
    (net (code "33") (name "Net-(IC26C-A)") (class "Default")
      (node (ref "IC26") (pin "10") (pinfunction "B_10") (pintype "input"))
      (node (ref "IC26") (pin "11") (pinfunction "~{O}_11") (pintype "output"))
      (node (ref "IC26") (pin "9") (pinfunction "A_9") (pintype "input"))
    )
    (net (code "34") (name "Net-(IC27-Q)") (class "Default")
      (node (ref "IC27") (pin "5") (pinfunction "Q_5") (pintype "output"))
      (node (ref "R126") (pin "1") (pinfunction "1_1") (pintype "passive"))
      (node (ref "R127") (pin "1") (pinfunction "1_1") (pintype "passive"))
    )
    (net (code "35") (name "Net-(IC27-~{RD})") (class "Default")
      (node (ref "C103") (pin "2") (pinfunction "2_2") (pintype "passive"))
      (node (ref "IC27") (pin "6") (pinfunction "~{RD}_6") (pintype "input"))
      (node (ref "R131") (pin "1") (pinfunction "1_1") (pintype "passive"))
    )
    (net (code "36") (name "Net-(LD1A-C)") (class "Default")
      (node (ref "LD1") (pin "1") (pinfunction "C_1") (pintype "passive"))
      (node (ref "R151") (pin "2") (pinfunction "2_2") (pintype "passive"))
    )
    (net (code "37") (name "Net-(LD1B-C)") (class "Default")
      (node (ref "LD1") (pin "3") (pinfunction "C_3") (pintype "passive"))
      (node (ref "R152") (pin "2") (pinfunction "2_2") (pintype "passive"))
    )
    (net (code "38") (name "Net-(LD3A-A)") (class "Default")
      (node (ref "LD3") (pin "2") (pinfunction "A_2") (pintype "passive"))
      (node (ref "R13") (pin "1") (pinfunction "1_1") (pintype "passive"))
    )
    (net (code "39") (name "Net-(LD3A-C)") (class "Default")
      (node (ref "LD3") (pin "1") (pinfunction "C_1") (pintype "passive"))
      (node (ref "T12") (pin "3") (pinfunction "C_3") (pintype "passive"))
    )
    (net (code "40") (name "Net-(LD3B-A)") (class "Default")
      (node (ref "LD3") (pin "4") (pinfunction "A_4") (pintype "passive"))
      (node (ref "R15") (pin "1") (pinfunction "1_1") (pintype "passive"))
    )
    (net (code "41") (name "Net-(R50-Pad1)") (class "Default")
      (node (ref "R50") (pin "1") (pinfunction "1_1") (pintype "passive"))
      (node (ref "R51") (pin "2") (pinfunction "2_2") (pintype "passive"))
    )
    (net (code "42") (name "Net-(R53-Pad1)") (class "Default")
      (node (ref "R53") (pin "1") (pinfunction "1_1") (pintype "passive"))
      (node (ref "R54") (pin "2") (pinfunction "2_2") (pintype "passive"))
    )
    (net (code "43") (name "Net-(R66-Pad1)") (class "Default")
      (node (ref "R66") (pin "1") (pinfunction "1_1") (pintype "passive"))
      (node (ref "R68") (pin "2") (pinfunction "2_2") (pintype "passive"))
    )
    (net (code "44") (name "Net-(RL1B-NO)") (class "Default")
      (node (ref "R115") (pin "1") (pinfunction "1_1") (pintype "passive"))
      (node (ref "RL1") (pin "4") (pinfunction "NO_4") (pintype "bidirectional"))
      (node (ref "RL1") (pin "5") (pinfunction "NO_5") (pintype "bidirectional"))
    )
    (net (code "45") (name "Net-(RL2B-NC)") (class "Default")
      (node (ref "R130") (pin "1") (pinfunction "1_1") (pintype "passive"))
      (node (ref "RL2") (pin "2") (pinfunction "NC_2") (pintype "bidirectional"))
      (node (ref "RL2") (pin "7") (pinfunction "NC_7") (pintype "bidirectional"))
    )
    (net (code "46") (name "Net-(T11-C)") (class "Default")
      (node (ref "T11") (pin "3") (pinfunction "C_3") (pintype "passive"))
      (node (ref "T13") (pin "2") (pinfunction "E_2") (pintype "passive"))
    )
    (net (code "47") (name "Net-(T13-B)") (class "Default")
      (node (ref "R117") (pin "2") (pinfunction "2_2") (pintype "passive"))
      (node (ref "R120") (pin "1") (pinfunction "1_1") (pintype "passive"))
      (node (ref "T13") (pin "1") (pinfunction "B_1") (pintype "passive"))
      (node (ref "T14") (pin "3") (pinfunction "C_3") (pintype "passive"))
    )
    (net (code "48") (name "Net-(T14-B)") (class "Default")
      (node (ref "R119") (pin "2") (pinfunction "2_2") (pintype "passive"))
      (node (ref "T14") (pin "1") (pinfunction "B_1") (pintype "passive"))
    )
    (net (code "49") (name "Net-(T15-B)") (class "Default")
      (node (ref "R126") (pin "2") (pinfunction "2_2") (pintype "passive"))
      (node (ref "R128") (pin "1") (pinfunction "1_1") (pintype "passive"))
      (node (ref "T15") (pin "1") (pinfunction "B_1") (pintype "passive"))
    )
    (net (code "50") (name "P1V5REF") (class "Default")
      (node (ref "C89") (pin "2") (pinfunction "2_2") (pintype "passive"))
      (node (ref "IC6") (pin "1") (pinfunction "C_1") (pintype "passive"))
      (node (ref "R49") (pin "1") (pinfunction "1_1") (pintype "passive"))
      (node (ref "R52") (pin "1") (pinfunction "1_1") (pintype "passive"))
      (node (ref "R53") (pin "2") (pinfunction "2_2") (pintype "passive"))
      (node (ref "R65") (pin "1") (pinfunction "1_1") (pintype "passive"))
    )
    (net (code "51") (name "P3V3s") (class "Default")
      (node (ref "C10") (pin "2") (pinfunction "2_2") (pintype "passive"))
      (node (ref "C115") (pin "2") (pinfunction "2_2") (pintype "passive"))
      (node (ref "IC26") (pin "12") (pinfunction "A_12") (pintype "input"))
      (node (ref "IC26") (pin "13") (pinfunction "B_13") (pintype "input"))
      (node (ref "IC26") (pin "14") (pinfunction "VCC_14") (pintype "power_in"))
      (node (ref "IC27") (pin "7") (pinfunction "~{S}D_7") (pintype "input"))
      (node (ref "IC27") (pin "8") (pinfunction "VCC_8") (pintype "power_in"))
      (node (ref "R109") (pin "2") (pinfunction "2_2") (pintype "passive"))
      (node (ref "R121") (pin "2") (pinfunction "2_2") (pintype "passive"))
      (node (ref "R13") (pin "2") (pinfunction "2_2") (pintype "passive"))
      (node (ref "R131") (pin "2") (pinfunction "2_2") (pintype "passive"))
    )
    (net (code "52") (name "P12V0") (class "Default")
      (node (ref "D4") (pin "2") (pinfunction "C_2") (pintype "passive"))
      (node (ref "D5") (pin "2") (pinfunction "C_2") (pintype "passive"))
      (node (ref "LD1") (pin "2") (pinfunction "A_2") (pintype "passive"))
      (node (ref "LD1") (pin "4") (pinfunction "A_4") (pintype "passive"))
      (node (ref "R156") (pin "2") (pinfunction "2_2") (pintype "passive"))
      (node (ref "R52") (pin "2") (pinfunction "2_2") (pintype "passive"))
      (node (ref "RL1") (pin "1") (pinfunction "1_1") (pintype "passive"))
      (node (ref "RL2") (pin "1") (pinfunction "1_1") (pintype "passive"))
    )
    (net (code "53") (name "P14V5LASER") (class "Default")
      (node (ref "D6") (pin "3") (pinfunction "C_3") (pintype "passive"))
    )
    (net (code "54") (name "unconnected-(D4A-A-Pad1)") (class "Default")
      (node (ref "D4") (pin "1") (pinfunction "A_1") (pintype "passive+no_connect"))
    )
    (net (code "55") (name "unconnected-(D4A-COMAC-Pad3)") (class "Default")
      (node (ref "D4") (pin "3") (pinfunction "COMAC_3") (pintype "passive+no_connect"))
    )
    (net (code "56") (name "unconnected-(D5A-A-Pad1)") (class "Default")
      (node (ref "D5") (pin "1") (pinfunction "A_1") (pintype "passive+no_connect"))
    )
    (net (code "57") (name "unconnected-(D5A-COMAC-Pad3)") (class "Default")
      (node (ref "D5") (pin "3") (pinfunction "COMAC_3") (pintype "passive+no_connect"))
    )
    (net (code "58") (name "unconnected-(IC6-NC-Pad4)") (class "Default")
      (node (ref "IC6") (pin "4") (pinfunction "NC_4") (pintype "passive"))
    )
    (net (code "59") (name "unconnected-(IC6-NC-Pad5)") (class "Default")
      (node (ref "IC6") (pin "5") (pinfunction "NC_5") (pintype "passive"))
    )
    (net (code "60") (name "unconnected-(IC26C-~{O}-Pad8)") (class "Default")
      (node (ref "IC26") (pin "8") (pinfunction "~{O}_8") (pintype "output+no_connect"))
    )
    (net (code "61") (name "unconnected-(IC27-~{Q}-Pad3)") (class "Default")
      (node (ref "IC27") (pin "3") (pinfunction "~{Q}_3") (pintype "output+no_connect"))
    )
  )
)
